# 02-Power.net
KiCad netlist of a schematic drawn in Altium Designer
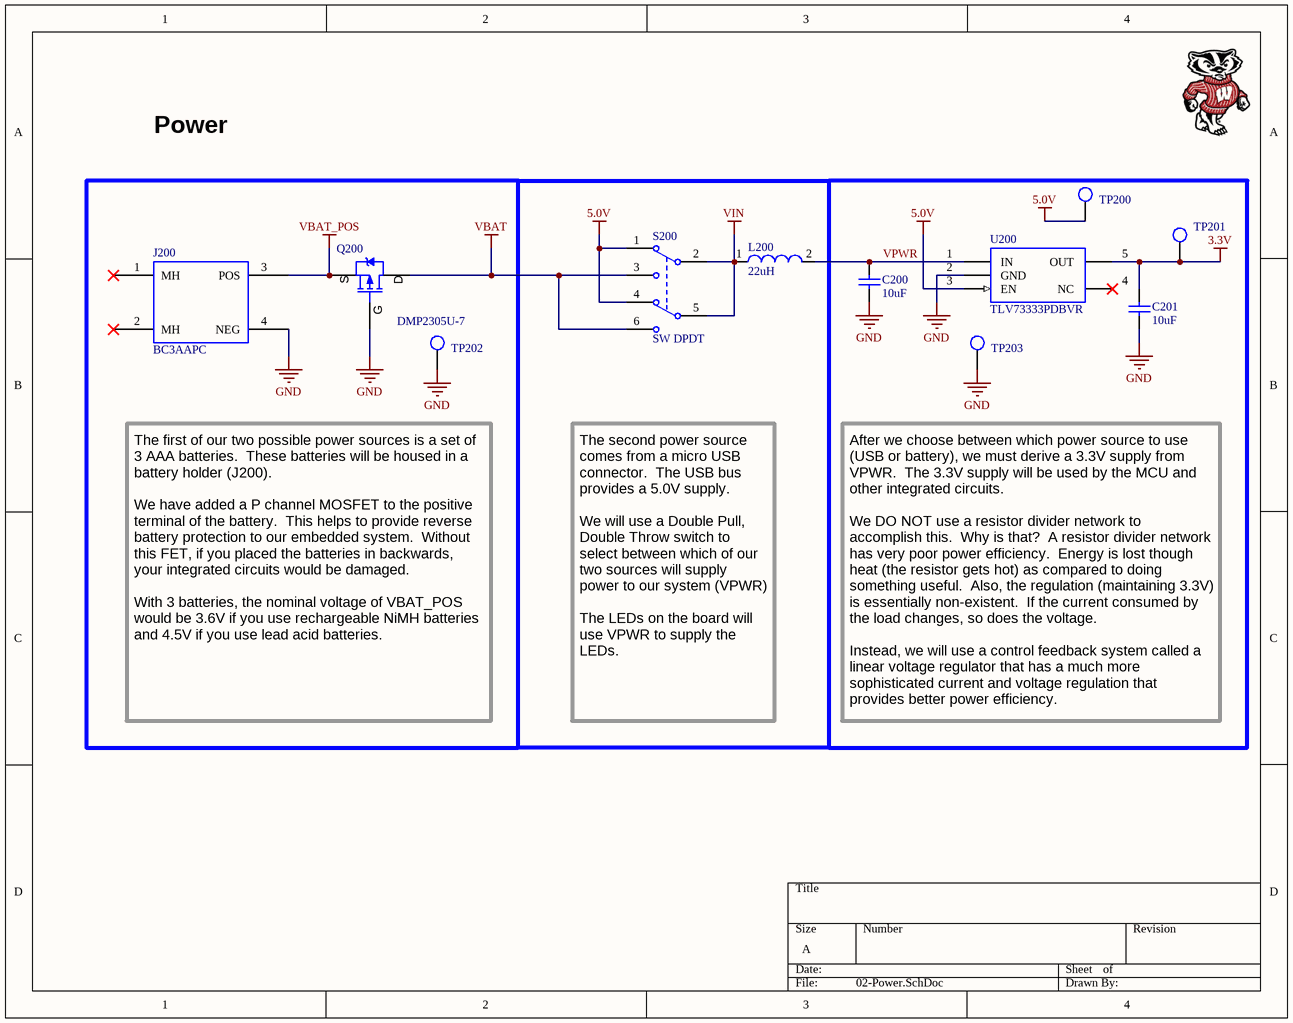
[diagram p0: 02-Power.SchDoc]

(export (version "E")
  (design (tool "Eeschema 10.0.6"))
  (components
    (comp (ref "C200")
      (value "10uF")
      (footprint "CAP_0805")
      (description "CAP CER 10UF 16V X7R 0805")
      (fields
        (field (name "MANUFACTURER") "Samsung")
        (field (name "MANUFACTURER PART NUMBER") "CL21A106KPCLQNC")
        (field (name "CAPACITANCE") "10uF")
      )
      (libsource (lib "ece315-S20") (part "CAP_0805_U_010.00"))
    )
    (comp (ref "C201")
      (value "10uF")
      (footprint "CAP_0805")
      (description "CAP CER 10UF 16V X7R 0805")
      (fields
        (field (name "MANUFACTURER") "Samsung")
        (field (name "MANUFACTURER PART NUMBER") "CL21A106KPCLQNC")
        (field (name "CAPACITANCE") "10uF")
      )
      (libsource (lib "ece315-S20") (part "CAP_0805_U_010.00"))
    )
    (comp (ref "J200")
      (value "BC3AAPC")
      (footprint "BC3AAPC")
      (description "BATTERY HOLDER AA 3 CELL PC PIN")
      (fields
        (field (name "MANUFACTURER") "Memory Protection Devices")
        (field (name "MANUFACTURER PART NUMBER") "BC3AAPC")
      )
      (libsource (lib "Battery") (part "BC3AAPC"))
    )
    (comp (ref "L200")
      (value "SRN3015-220M")
      (footprint "SRN3015")
      (description "22uH 3x3mm sheilded inductor 600mA")
      (fields (field (name "TOLERANCE") "20%") (field (name "INDUCTANCE") "22uH"))
      (libsource (lib "Inductors") (part "SRN3015-220M"))
    )
    (comp (ref "Q200")
      (value "PMOS-DMP2305U-7")
      (footprint "SOT23")
      (description "MOSFET P-CH 20V 4.2A SOT-23")
      (fields
        (field (name "MANUFACTURER") "Diodes Zetex")
        (field (name "MANUFACTURER PART NUMBER") "DMP2305U-7")
      )
      (libsource (lib "Transistors") (part "PMOS-DMP2305U-7"))
    )
    (comp (ref "S200")
      (value "SW DPDT")
      (footprint "DPDT")
      (description "Switch")
      (fields
        (field (name "MANUFACTURER") "ITT /  C&K Components")
        (field (name "MANUFACTURER PART NUMBER") "JS202011SCQN")
        (field (name "PUBLISHER") "Altium Limited")
      )
      (libsource (lib "ece315-2018-fall") (part "SW DPDT"))
    )
    (comp (ref "TP200")
      (value "TP_1206")
      (footprint "TP-SMC-1206")
      (description "Test Point SMD 1206")
      (fields
        (field (name "MANUFACTURER") "TE Connectivity (Tyco Electronics)")
        (field (name "MANUFACTURER PART NUMBER") "1625854-1")
      )
      (libsource (lib "ece315-S20") (part "TP_1206"))
    )
    (comp (ref "TP201")
      (value "TP_1206")
      (footprint "TP-SMC-1206")
      (description "Test Point SMD 1206")
      (fields
        (field (name "MANUFACTURER") "TE Connectivity (Tyco Electronics)")
        (field (name "MANUFACTURER PART NUMBER") "1625854-1")
      )
      (libsource (lib "ece315-S20") (part "TP_1206"))
    )
    (comp (ref "TP202")
      (value "TP_1206")
      (footprint "TP-SMC-1206")
      (description "Test Point SMD 1206")
      (fields
        (field (name "MANUFACTURER") "TE Connectivity (Tyco Electronics)")
        (field (name "MANUFACTURER PART NUMBER") "1625854-1")
      )
      (libsource (lib "ece315-S20") (part "TP_1206"))
    )
    (comp (ref "TP203")
      (value "TP_1206")
      (footprint "TP-SMC-1206")
      (description "Test Point SMD 1206")
      (fields
        (field (name "MANUFACTURER") "TE Connectivity (Tyco Electronics)")
        (field (name "MANUFACTURER PART NUMBER") "1625854-1")
      )
      (libsource (lib "ece315-S20") (part "TP_1206"))
    )
    (comp (ref "U200")
      (value "IC-TLV733P")
      (footprint "SOT23_TLV733")
      (description "IC REG LINEAR 3.3V 300MA SOT23-5")
      (fields
        (field (name "MANUFACTURER") "Texas Instruments")
        (field (name "MANUFACTURER PART NUMBER") "TLV73333PDBVR")
      )
      (libsource (lib "ece315-S20") (part "IC-TLV733P"))
    )
  )
  (nets
    (net (code "1") (name "/VPWR") (class "Default")
      (node (ref "C200") (pin "2") (pinfunction "2_2") (pintype "passive"))
      (node (ref "L200") (pin "2") (pinfunction "1_2") (pintype "passive"))
      (node (ref "U200") (pin "1") (pinfunction "IN_1") (pintype "power_in"))
    )
    (net (code "2") (name "3.3V") (class "Default")
      (node (ref "C201") (pin "2") (pinfunction "2_2") (pintype "passive"))
      (node (ref "TP201") (pin "1") (pintype "passive"))
      (node (ref "U200") (pin "5") (pinfunction "OUT_5") (pintype "power_in"))
    )
    (net (code "3") (name "5.0V") (class "Default")
      (node (ref "S200") (pin "1") (pinfunction "NC1_1") (pintype "passive"))
      (node (ref "S200") (pin "4") (pinfunction "NC2_4") (pintype "passive"))
      (node (ref "TP200") (pin "1") (pintype "passive"))
      (node (ref "U200") (pin "3") (pinfunction "EN_3") (pintype "input"))
    )
    (net (code "4") (name "GND") (class "Default")
      (node (ref "C200") (pin "1") (pinfunction "1_1") (pintype "passive"))
      (node (ref "C201") (pin "1") (pinfunction "1_1") (pintype "passive"))
      (node (ref "J200") (pin "4") (pinfunction "NEG_4") (pintype "power_in"))
      (node (ref "Q200") (pin "1") (pinfunction "G_1") (pintype "passive"))
      (node (ref "TP202") (pin "1") (pintype "passive"))
      (node (ref "TP203") (pin "1") (pintype "passive"))
      (node (ref "U200") (pin "2") (pinfunction "GND_2") (pintype "power_in"))
    )
    (net (code "5") (name "VBAT") (class "Default")
      (node (ref "Q200") (pin "3") (pinfunction "D_3") (pintype "passive"))
      (node (ref "S200") (pin "3") (pinfunction "NO1_3") (pintype "passive"))
      (node (ref "S200") (pin "6") (pinfunction "NO2_6") (pintype "passive"))
    )
    (net (code "6") (name "VBAT_POS") (class "Default")
      (node (ref "J200") (pin "3") (pinfunction "POS_3") (pintype "power_in"))
      (node (ref "Q200") (pin "2") (pinfunction "S_2") (pintype "passive"))
    )
    (net (code "7") (name "VIN") (class "Default")
      (node (ref "L200") (pin "1") (pinfunction "0_1") (pintype "passive"))
      (node (ref "S200") (pin "2") (pinfunction "COMMON1_2") (pintype "passive"))
      (node (ref "S200") (pin "5") (pinfunction "COMMON2_5") (pintype "passive"))
    )
    (net (code "8") (name "unconnected-(J200-MH-Pad1)") (class "Default")
      (node (ref "J200") (pin "1") (pinfunction "MH_1") (pintype "passive+no_connect"))
    )
    (net (code "9") (name "unconnected-(J200-MH-Pad2)") (class "Default")
      (node (ref "J200") (pin "2") (pinfunction "MH_2") (pintype "passive+no_connect"))
    )
    (net (code "10") (name "unconnected-(U200-NC-Pad4)") (class "Default")
      (node (ref "U200") (pin "4") (pinfunction "NC_4") (pintype "passive+no_connect"))
    )
  )
)
